# 5V_MAIN.net
KiCad netlist of a schematic drawn in Altium Designer
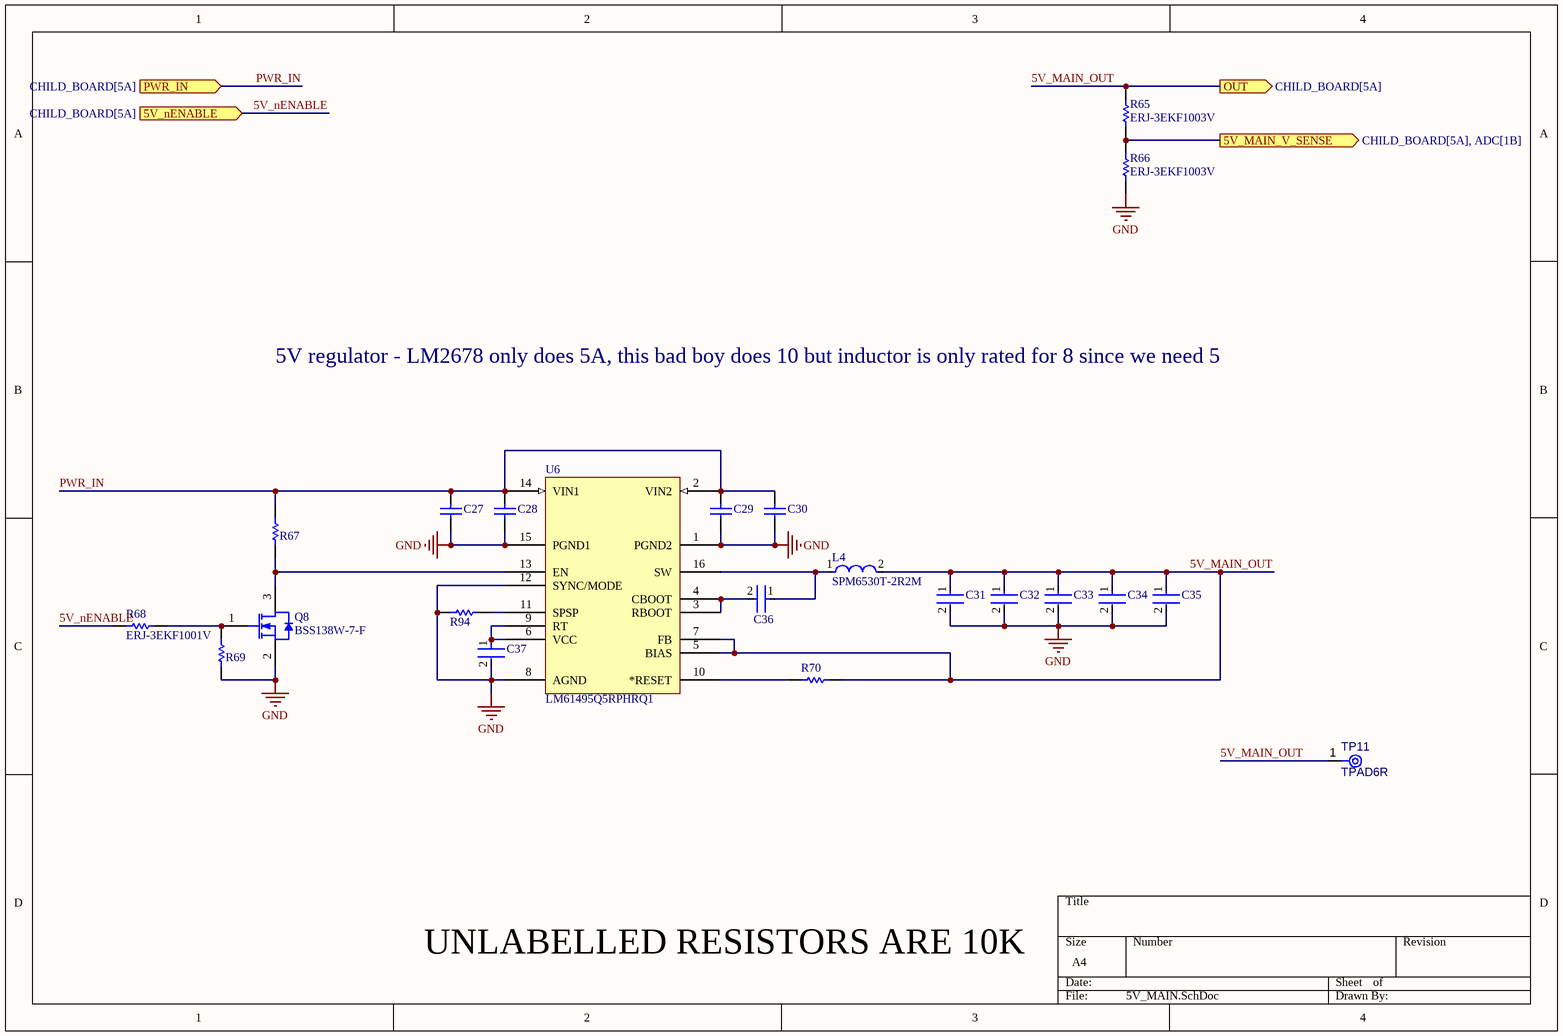
[diagram p0: 5V_MAIN.SchDoc]

(export (version "E")
  (design (tool "Eeschema 10.0.6"))
  (components
    (comp (ref "C27")
      (value "GRM219R61E106KA12D")
      (footprint "CAPC2013X95X45ML10T25")
      (fields (field (name "MANUFACTURER") "Murata"))
      (libsource (lib "Altium Content Vault") (part "CAP"))
    )
    (comp (ref "C28")
      (value "CAP 470nF 50V 1812(4532)")
      (footprint "CAPC1812(4532)125_M")
      (description "CAP 470nF 50V ±10% 1812 (4532 Metric) Thickness 1.25mm SMD")
      (fields (field (name "TOLERANCE") "Â±10%"))
      (libsource (lib "Altium Content Vault") (part "CAP"))
    )
    (comp (ref "C29")
      (value "CAP 470nF 50V 1812(4532)")
      (footprint "CAPC1812(4532)125_M")
      (description "CAP 470nF 50V ±10% 1812 (4532 Metric) Thickness 1.25mm SMD")
      (fields (field (name "TOLERANCE") "Â±10%"))
      (libsource (lib "Altium Content Vault") (part "CAP"))
    )
    (comp (ref "C30")
      (value "GRM219R61E106KA12D")
      (footprint "CAPC2013X95X45ML10T25")
      (fields (field (name "MANUFACTURER") "Murata"))
      (libsource (lib "Altium Content Vault") (part "CAP"))
    )
    (comp (ref "C31")
      (value "GRM21BR61E226ME44L")
      (footprint "FP-GRM21B-0_2-e0_2_0_7-IPC_B")
      (description "Chip Multilayer Ceramic Capacitors for General Purpose, 0805, 22uF, X5R, 15%, 20%, 25V")
      (fields (field (name "TOLERANCE") "20%") (field (name "VOLTAGE") "25V"))
      (libsource (lib "Altium Content Vault") (part "b4654b650e69147ec39a6b967a45e02"))
    )
    (comp (ref "C32")
      (value "GRM21BR61E226ME44L")
      (footprint "FP-GRM21B-0_2-e0_2_0_7-IPC_B")
      (description "Chip Multilayer Ceramic Capacitors for General Purpose, 0805, 22uF, X5R, 15%, 20%, 25V")
      (fields (field (name "TOLERANCE") "20%") (field (name "VOLTAGE") "25V"))
      (libsource (lib "Altium Content Vault") (part "b4654b650e69147ec39a6b967a45e02"))
    )
    (comp (ref "C33")
      (value "GRM21BR61E226ME44L")
      (footprint "FP-GRM21B-0_2-e0_2_0_7-IPC_B")
      (description "Chip Multilayer Ceramic Capacitors for General Purpose, 0805, 22uF, X5R, 15%, 20%, 25V")
      (fields (field (name "TOLERANCE") "20%") (field (name "VOLTAGE") "25V"))
      (libsource (lib "Altium Content Vault") (part "b4654b650e69147ec39a6b967a45e02"))
    )
    (comp (ref "C34")
      (value "GRM21BR61E226ME44L")
      (footprint "FP-GRM21B-0_2-e0_2_0_7-IPC_B")
      (description "Chip Multilayer Ceramic Capacitors for General Purpose, 0805, 22uF, X5R, 15%, 20%, 25V")
      (fields (field (name "TOLERANCE") "20%") (field (name "VOLTAGE") "25V"))
      (libsource (lib "Altium Content Vault") (part "b4654b650e69147ec39a6b967a45e02"))
    )
    (comp (ref "C35")
      (value "GRM21BR61E226ME44L")
      (footprint "FP-GRM21B-0_2-e0_2_0_7-IPC_B")
      (description "Chip Multilayer Ceramic Capacitors for General Purpose, 0805, 22uF, X5R, 15%, 20%, 25V")
      (fields (field (name "TOLERANCE") "20%") (field (name "VOLTAGE") "25V"))
      (libsource (lib "Altium Content Vault") (part "b4654b650e69147ec39a6b967a45e02"))
    )
    (comp (ref "C36")
      (value "C1005X7R1H104K050BB")
      (footprint "FP-C1005-050-0_05-IPC_C")
      (description "Multilayer Ceramic Capacitors 100nF ±10% 50V X7R SMD 0402")
      (fields (field (name "VOLTAGE") "50V") (field (name "TOLERANCE") "10%"))
      (libsource (lib "Altium Content Vault") (part "b4654b650e69147ec39a6b967a45e02"))
    )
    (comp (ref "C37")
      (value "UMK107AB7105KA-T")
      (footprint "FP-0603-L_1_6_0_15-W_0_8-IPC_C")
      (description "Ceramic Capacitor General Use 1uF ±10% 50V X7R 0603")
      (fields (field (name "TOLERANCE") "10%"))
      (libsource (lib "Altium Content Vault") (part "11868f565c42a9108669ba33697ecf6"))
    )
    (comp (ref "L4")
      (value "SPM6530T-2R2M")
      (footprint "FP-SPM6530-MFG")
      (description "FIXED IND 2.2UH 8.2A 19 MOHM SMD")
      (fields
        (field (name "OCTOPART") "https://octopart.com/spm6530t-2r2m-tdk-18903909")
        (field (name "MANUFACTURER") "TDK")
      )
      (libsource (lib "Altium Content Vault") (part "725321dda6339637d4d059423bc1c3c"))
    )
    (comp (ref "Q8")
      (value "BSS138W-7-F")
      (footprint "DIOD-SOT323-3_V")
      (fields (field (name "MANUFACTURER") "DiodesIncorporated"))
      (libsource (lib "Altium Content Vault") (part "NEMOS-GSD-3"))
    )
    (comp (ref "R65")
      (value "ERJ-3EKF1003V")
      (footprint "RESC1608X55X30ML15T15")
      (fields (field (name "MANUFACTURER") "Panasonic"))
      (libsource (lib "Altium Content Vault") (part "RES"))
    )
    (comp (ref "R66")
      (value "ERJ-3EKF1003V")
      (footprint "RESC1608X55X30ML15T15")
      (fields (field (name "MANUFACTURER") "Panasonic"))
      (libsource (lib "Altium Content Vault") (part "RES"))
    )
    (comp (ref "R67")
      (value "ERJ3EKF1002V")
      (footprint "RESC1609X55X30LL15T15")
      (description "Chip Resistor, 10 KOhm, +/- 1%, 0.1 W, -55 to 155 degC, 0603 (1608 Metric), RoHS, Tape and Reel")
      (fields (field (name "TOLERANCE") "1%") (field (name "MANUFACTURER") "Panasonic"))
      (libsource (lib "Altium Content Vault") (part "RES-2"))
    )
    (comp (ref "R68")
      (value "ERJ-3EKF1001V")
      (footprint "RESC1608X55X30LL15T15")
      (fields (field (name "MANUFACTURER") "Panasonic"))
      (libsource (lib "Altium Content Vault") (part "RES"))
    )
    (comp (ref "R69")
      (value "ERJ3EKF1002V")
      (footprint "RESC1609X55X30LL15T15")
      (description "Chip Resistor, 10 KOhm, +/- 1%, 0.1 W, -55 to 155 degC, 0603 (1608 Metric), RoHS, Tape and Reel")
      (fields (field (name "TOLERANCE") "1%") (field (name "MANUFACTURER") "Panasonic"))
      (libsource (lib "Altium Content Vault") (part "RES-2"))
    )
    (comp (ref "R70")
      (value "ERJ3EKF1002V")
      (footprint "RESC1609X55X30LL15T15")
      (description "Chip Resistor, 10 KOhm, +/- 1%, 0.1 W, -55 to 155 degC, 0603 (1608 Metric), RoHS, Tape and Reel")
      (fields (field (name "TOLERANCE") "1%") (field (name "MANUFACTURER") "Panasonic"))
      (libsource (lib "Altium Content Vault") (part "RES-2"))
    )
    (comp (ref "R94")
      (value "ERJ3EKF1002V")
      (footprint "RESC1609X55X30LL15T15")
      (description "Chip Resistor, 10 KOhm, +/- 1%, 0.1 W, -55 to 155 degC, 0603 (1608 Metric), RoHS, Tape and Reel")
      (fields (field (name "TOLERANCE") "1%") (field (name "MANUFACTURER") "Panasonic"))
      (libsource (lib "Altium Content Vault") (part "RES-2"))
    )
    (comp (ref "TP11")
      (value "TPAD6R")
      (footprint "TP06R")
      (description "0.6mm round")
      (libsource (lib "uORocketry Hardware") (part "CMP-001-0001-4"))
    )
    (comp (ref "U6")
      (value "LM61495Q5RPHRQ1")
      (footprint "LM61495Q5RPHRQ1-Footprint-1")
      (description "10-A automotive buck converter optimized for power density and low EMI 16-VQFN-HR -40 to 150")
      (libsource (lib "uORocketry Hardware") (part "LM61495Q5RPHRQ1"))
    )
  )
  (nets
    (net (code "1") (name "/5V_MAIN_OUT") (class "Default")
      (node (ref "C31") (pin "1") (pinfunction "1_1") (pintype "passive"))
      (node (ref "C32") (pin "1") (pinfunction "1_1") (pintype "passive"))
      (node (ref "C33") (pin "1") (pinfunction "1_1") (pintype "passive"))
      (node (ref "C34") (pin "1") (pinfunction "1_1") (pintype "passive"))
      (node (ref "C35") (pin "1") (pinfunction "1_1") (pintype "passive"))
      (node (ref "L4") (pin "2") (pinfunction "2_2") (pintype "passive"))
      (node (ref "R65") (pin "2") (pinfunction "2_2") (pintype "passive"))
      (node (ref "R70") (pin "2") (pinfunction "2_2") (pintype "passive"))
      (node (ref "TP11") (pin "1") (pinfunction "TP_1") (pintype "passive"))
      (node (ref "U6") (pin "5") (pinfunction "BIAS_5") (pintype "passive"))
      (node (ref "U6") (pin "7") (pinfunction "FB_7") (pintype "passive"))
    )
    (net (code "2") (name "/5V_MAIN_V_SENSE") (class "Default")
      (node (ref "R65") (pin "1") (pinfunction "1_1") (pintype "passive"))
      (node (ref "R66") (pin "2") (pinfunction "2_2") (pintype "passive"))
    )
    (net (code "3") (name "/5V_nENABLE") (class "Default")
      (node (ref "R68") (pin "1") (pinfunction "1_1") (pintype "passive"))
    )
    (net (code "4") (name "/PWR_IN") (class "Default")
      (node (ref "C27") (pin "2") (pinfunction "2_2") (pintype "passive"))
      (node (ref "C28") (pin "2") (pinfunction "2_2") (pintype "passive"))
      (node (ref "C29") (pin "2") (pinfunction "2_2") (pintype "passive"))
      (node (ref "C30") (pin "2") (pinfunction "2_2") (pintype "passive"))
      (node (ref "R67") (pin "2") (pinfunction "2_2") (pintype "passive"))
      (node (ref "U6") (pin "14") (pinfunction "VIN1_14") (pintype "input"))
      (node (ref "U6") (pin "2") (pinfunction "VIN2_2") (pintype "input"))
    )
    (net (code "5") (name "GND") (class "Default")
      (node (ref "C27") (pin "1") (pinfunction "1_1") (pintype "passive"))
      (node (ref "C28") (pin "1") (pinfunction "1_1") (pintype "passive"))
      (node (ref "C29") (pin "1") (pinfunction "1_1") (pintype "passive"))
      (node (ref "C30") (pin "1") (pinfunction "1_1") (pintype "passive"))
      (node (ref "C31") (pin "2") (pinfunction "2_2") (pintype "passive"))
      (node (ref "C32") (pin "2") (pinfunction "2_2") (pintype "passive"))
      (node (ref "C33") (pin "2") (pinfunction "2_2") (pintype "passive"))
      (node (ref "C34") (pin "2") (pinfunction "2_2") (pintype "passive"))
      (node (ref "C35") (pin "2") (pinfunction "2_2") (pintype "passive"))
      (node (ref "C37") (pin "2") (pinfunction "2_2") (pintype "passive"))
      (node (ref "Q8") (pin "2") (pinfunction "S_2") (pintype "passive"))
      (node (ref "R66") (pin "1") (pinfunction "1_1") (pintype "passive"))
      (node (ref "R69") (pin "1") (pinfunction "1_1") (pintype "passive"))
      (node (ref "R94") (pin "2") (pinfunction "2_2") (pintype "passive"))
      (node (ref "U6") (pin "1") (pinfunction "PGND2_1") (pintype "power_in"))
      (node (ref "U6") (pin "12") (pinfunction "SYNC/MODE_12") (pintype "passive"))
      (node (ref "U6") (pin "15") (pinfunction "PGND1_15") (pintype "power_in"))
      (node (ref "U6") (pin "8") (pinfunction "AGND_8") (pintype "power_in"))
    )
    (net (code "6") (name "Net-(Q8-D)") (class "Default")
      (node (ref "Q8") (pin "3") (pinfunction "D_3") (pintype "passive"))
      (node (ref "R67") (pin "1") (pinfunction "1_1") (pintype "passive"))
      (node (ref "U6") (pin "13") (pinfunction "EN_13") (pintype "passive"))
    )
    (net (code "7") (name "Net-(Q8-G)") (class "Default")
      (node (ref "Q8") (pin "1") (pinfunction "G_1") (pintype "passive"))
      (node (ref "R68") (pin "2") (pinfunction "2_2") (pintype "passive"))
      (node (ref "R69") (pin "2") (pinfunction "2_2") (pintype "passive"))
    )
    (net (code "8") (name "Net-(U6-*RESET)") (class "Default")
      (node (ref "R70") (pin "1") (pinfunction "1_1") (pintype "passive"))
      (node (ref "U6") (pin "10") (pinfunction "*RESET_10") (pintype "passive"))
    )
    (net (code "9") (name "Net-(U6-CBOOT)") (class "Default")
      (node (ref "C36") (pin "2") (pinfunction "2_2") (pintype "passive"))
      (node (ref "U6") (pin "3") (pinfunction "RBOOT_3") (pintype "passive"))
      (node (ref "U6") (pin "4") (pinfunction "CBOOT_4") (pintype "passive"))
    )
    (net (code "10") (name "Net-(U6-RT)") (class "Default")
      (node (ref "C37") (pin "1") (pinfunction "1_1") (pintype "passive"))
      (node (ref "U6") (pin "6") (pinfunction "VCC_6") (pintype "power_in"))
      (node (ref "U6") (pin "9") (pinfunction "RT_9") (pintype "passive"))
    )
    (net (code "11") (name "Net-(U6-SPSP)") (class "Default")
      (node (ref "R94") (pin "1") (pinfunction "1_1") (pintype "passive"))
      (node (ref "U6") (pin "11") (pinfunction "SPSP_11") (pintype "passive"))
    )
    (net (code "12") (name "Net-(U6-SW)") (class "Default")
      (node (ref "C36") (pin "1") (pinfunction "1_1") (pintype "passive"))
      (node (ref "L4") (pin "1") (pinfunction "1_1") (pintype "passive"))
      (node (ref "U6") (pin "16") (pinfunction "SW_16") (pintype "passive"))
    )
  )
)
